# Qwiic_Hall_Effect_Sensor_TMAG5273.net
KiCad netlist of a schematic drawn in EAGLE
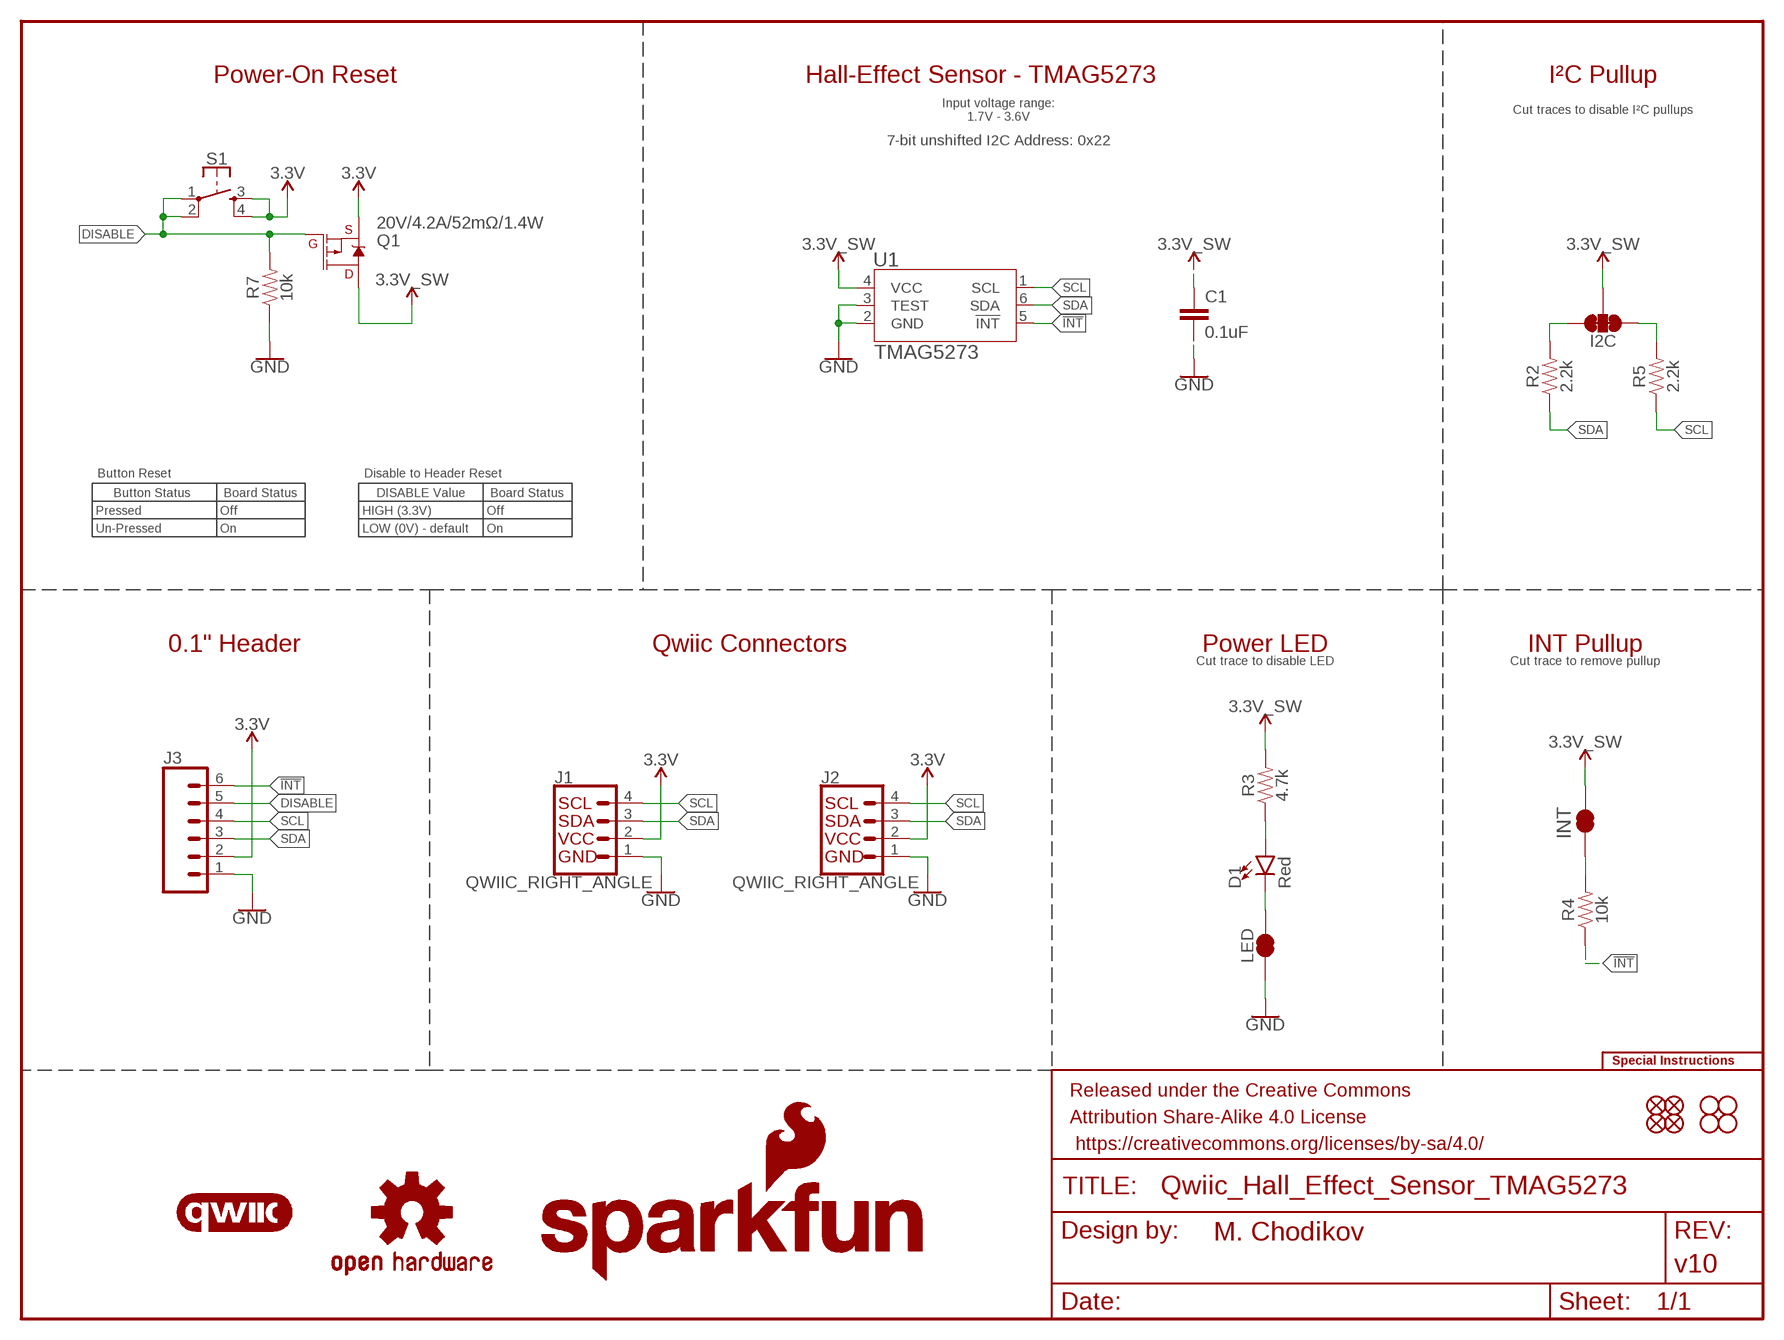
[diagram p0: schematic, sheet 1]

(export (version "E")
  (design (tool "Eeschema 10.0.6"))
  (components
    (comp (ref "C1")
      (value "0.1uF")
      (footprint "eagle-import:0603")
      (libsource (lib "eagle-import") (part "0.1UF-0603-25V-10%-X7R-WE"))
    )
    (comp (ref "D1")
      (value "Red")
      (footprint "eagle-import:LED-0603")
      (libsource (lib "eagle-import") (part "LED-RED_0603-KB"))
    )
    (comp (ref "FD1")
      (value "FIDUCIAL1X2")
      (footprint "eagle-import:FIDUCIAL-1X2")
      (libsource (lib "eagle-import") (part "FIDUCIAL1X2"))
    )
    (comp (ref "FD2")
      (value "FIDUCIAL1X2")
      (footprint "eagle-import:FIDUCIAL-1X2")
      (libsource (lib "eagle-import") (part "FIDUCIAL1X2"))
    )
    (comp (ref "FD3")
      (value "FIDUCIAL1X2")
      (footprint "eagle-import:FIDUCIAL-1X2")
      (libsource (lib "eagle-import") (part "FIDUCIAL1X2"))
    )
    (comp (ref "FD4")
      (value "FIDUCIAL1X2")
      (footprint "eagle-import:FIDUCIAL-1X2")
      (libsource (lib "eagle-import") (part "FIDUCIAL1X2"))
    )
    (comp (ref "FRAME1")
      (value "FRAME-LETTER")
      (footprint "eagle-import:CREATIVE_COMMONS")
      (fields (field (name "DESIGNER") "M. Chodikov") (field (name "REV") "v10"))
      (libsource (lib "eagle-import") (part "FRAME-LETTER"))
    )
    (comp (ref "H1")
      (value "STAND-OFF")
      (footprint "eagle-import:STAND-OFF")
      (libsource (lib "eagle-import") (part "STAND-OFF"))
    )
    (comp (ref "H2")
      (value "STAND-OFF")
      (footprint "eagle-import:STAND-OFF")
      (libsource (lib "eagle-import") (part "STAND-OFF"))
    )
    (comp (ref "H3")
      (value "STAND-OFF")
      (footprint "eagle-import:STAND-OFF")
      (libsource (lib "eagle-import") (part "STAND-OFF"))
    )
    (comp (ref "H4")
      (value "STAND-OFF")
      (footprint "eagle-import:STAND-OFF")
      (libsource (lib "eagle-import") (part "STAND-OFF"))
    )
    (comp (ref "I2C")
      (value "JUMPER-SMT_3_2-NC_TRACE_SILK")
      (footprint "eagle-import:SMT-JUMPER_3_2-NC_TRACE_SILK")
      (libsource (lib "eagle-import") (part "JUMPER-SMT_3_2-NC_TRACE_SILK"))
    )
    (comp (ref "J1")
      (value "QWIIC_RIGHT_ANGLE")
      (footprint "eagle-import:JST04_1MM_RA")
      (libsource (lib "eagle-import") (part "QWIIC_CONNECTORJS-1MM"))
    )
    (comp (ref "J2")
      (value "QWIIC_RIGHT_ANGLE")
      (footprint "eagle-import:JST04_1MM_RA")
      (libsource (lib "eagle-import") (part "QWIIC_CONNECTORJS-1MM"))
    )
    (comp (ref "J3")
      (value "CONN_06NO_SILK_FEMALE_PTH")
      (footprint "eagle-import:1X06_NO_SILK")
      (libsource (lib "eagle-import") (part "CONN_06NO_SILK_FEMALE_PTH"))
    )
    (comp (ref "JP2")
      (value "JUMPER-SMT_2_NC_TRACE_SILK")
      (footprint "eagle-import:SMT-JUMPER_2_NC_TRACE_SILK")
      (libsource (lib "eagle-import") (part "JUMPER-SMT_2_NC_TRACE_SILK"))
    )
    (comp (ref "LED")
      (value "JUMPER-SMT_2_NC_TRACE_SILK")
      (footprint "eagle-import:SMT-JUMPER_2_NC_TRACE_SILK")
      (libsource (lib "eagle-import") (part "JUMPER-SMT_2_NC_TRACE_SILK"))
    )
    (comp (ref "LOGO1")
      (value "OSHW-LOGOS")
      (footprint "eagle-import:OSHW-LOGO-S")
      (libsource (lib "eagle-import") (part "OSHW-LOGOS"))
    )
    (comp (ref "LOGO2")
      (value "SFE_LOGO_NAME_FLAME.1_INCH")
      (footprint "eagle-import:SFE_LOGO_NAME_FLAME_.1")
      (libsource (lib "eagle-import") (part "SFE_LOGO_NAME_FLAME.1_INCH"))
    )
    (comp (ref "LOGO3")
      (value "QWIIC_LOGO_4MM")
      (footprint "eagle-import:QWIIC_4MM")
      (libsource (lib "eagle-import") (part "QWIIC_LOGO_4MM"))
    )
    (comp (ref "LOGO4")
      (value "SFE_LOGO_NAME8_MM")
      (footprint "eagle-import:SFE_LOGO_NAME_8MM")
      (libsource (lib "eagle-import") (part "SFE_LOGO_NAME8_MM"))
    )
    (comp (ref "LOGO5")
      (value "SPECIAL_INSTRUCTIONS-ORDERING")
      (footprint "eagle-import:ORDERING_INSTRUCTIONS")
      (libsource (lib "eagle-import") (part "SPECIAL_INSTRUCTIONS-ORDERING"))
    )
    (comp (ref "LOGO6")
      (value "SFE_LOGO_FLAME.1_INCH")
      (footprint "eagle-import:SFE_LOGO_FLAME_.1")
      (libsource (lib "eagle-import") (part "SFE_LOGO_FLAME.1_INCH"))
    )
    (comp (ref "Q1")
      (value "20V/4.2A/52mΩ/1.4W")
      (footprint "eagle-import:SOT23-3")
      (libsource (lib "eagle-import") (part "MOSFET_PCH-DMG2305UX-7"))
    )
    (comp (ref "R2")
      (value "2.2k")
      (footprint "eagle-import:0603")
      (libsource (lib "eagle-import") (part "2.2KOHM-0603-1/10W-1%"))
    )
    (comp (ref "R3")
      (value "4.7k")
      (footprint "eagle-import:0603")
      (libsource (lib "eagle-import") (part "4.7KOHM-0603-1/10W-1%"))
    )
    (comp (ref "R4")
      (value "10k")
      (footprint "eagle-import:0603")
      (libsource (lib "eagle-import") (part "10KOHM-0603-1/10W-1%"))
    )
    (comp (ref "R5")
      (value "2.2k")
      (footprint "eagle-import:0603")
      (libsource (lib "eagle-import") (part "2.2KOHM-0603-1/10W-1%"))
    )
    (comp (ref "R7")
      (value "10k")
      (footprint "eagle-import:0603")
      (libsource (lib "eagle-import") (part "10KOHM-0603-1/10W-1%"))
    )
    (comp (ref "S1")
      (value "MOMENTARY-SWITCH-SPST-2-SMD-4.6X2.8MM")
      (footprint "eagle-import:TACTILE_SWITCH_SMD_4.6X2.8MM")
      (libsource (lib "eagle-import") (part "MOMENTARY-SWITCH-SPST-2-SMD-4.6X2.8MM"))
    )
    (comp (ref "U1")
      (value "TMAG5273")
      (footprint "eagle-import:SOT23-6_DBV_TEX")
      (libsource (lib "eagle-import") (part "TMAG5273A1QDBVT"))
    )
  )
  (nets
    (net (code "1") (name "/~{INT}") (class "Default")
      (node (ref "J3") (pin "6") (pinfunction "6_6") (pintype "passive"))
      (node (ref "R4") (pin "1") (pinfunction "1_1") (pintype "passive"))
      (node (ref "U1") (pin "5") (pinfunction "~{INT}_5") (pintype "bidirectional"))
    )
    (net (code "2") (name "3.3V") (class "Default")
      (node (ref "J1") (pin "2") (pinfunction "2_2") (pintype "power_in"))
      (node (ref "J2") (pin "2") (pinfunction "2_2") (pintype "power_in"))
      (node (ref "J3") (pin "2") (pinfunction "2_2") (pintype "passive"))
      (node (ref "Q1") (pin "2") (pinfunction "S_2") (pintype "bidirectional"))
      (node (ref "S1") (pin "3") (pinfunction "3_3") (pintype "passive"))
      (node (ref "S1") (pin "4") (pinfunction "4_4") (pintype "passive"))
    )
    (net (code "3") (name "3.3V_SW") (class "Default")
      (node (ref "C1") (pin "1") (pinfunction "1_1") (pintype "passive"))
      (node (ref "I2C") (pin "2") (pinfunction "2_2") (pintype "passive"))
      (node (ref "JP2") (pin "2") (pinfunction "2_2") (pintype "passive"))
      (node (ref "Q1") (pin "3") (pinfunction "D_3") (pintype "bidirectional"))
      (node (ref "R3") (pin "2") (pinfunction "2_2") (pintype "passive"))
      (node (ref "U1") (pin "4") (pinfunction "VCC_4") (pintype "power_in"))
    )
    (net (code "4") (name "DISABLE") (class "Default")
      (node (ref "J3") (pin "5") (pinfunction "5_5") (pintype "passive"))
      (node (ref "Q1") (pin "1") (pinfunction "G_1") (pintype "bidirectional"))
      (node (ref "R7") (pin "2") (pinfunction "2_2") (pintype "passive"))
      (node (ref "S1") (pin "1") (pinfunction "1_1") (pintype "passive"))
      (node (ref "S1") (pin "2") (pinfunction "2_2") (pintype "passive"))
    )
    (net (code "5") (name "GND") (class "Default")
      (node (ref "C1") (pin "2") (pinfunction "2_2") (pintype "passive"))
      (node (ref "J1") (pin "1") (pinfunction "1_1") (pintype "power_in"))
      (node (ref "J2") (pin "1") (pinfunction "1_1") (pintype "power_in"))
      (node (ref "J3") (pin "1") (pinfunction "1_1") (pintype "passive"))
      (node (ref "LED") (pin "1") (pinfunction "1_1") (pintype "passive"))
      (node (ref "R7") (pin "1") (pinfunction "1_1") (pintype "passive"))
      (node (ref "U1") (pin "2") (pinfunction "GND_2") (pintype "passive"))
      (node (ref "U1") (pin "3") (pinfunction "TEST_3") (pintype "input"))
    )
    (net (code "6") (name "Net-(D1-PadA)") (class "Default")
      (node (ref "D1") (pin "A") (pinfunction "A_A") (pintype "passive"))
      (node (ref "R3") (pin "1") (pinfunction "1_1") (pintype "passive"))
    )
    (net (code "7") (name "Net-(D1-PadC)") (class "Default")
      (node (ref "D1") (pin "C") (pinfunction "C_C") (pintype "passive"))
      (node (ref "LED") (pin "2") (pinfunction "2_2") (pintype "passive"))
    )
    (net (code "8") (name "Net-(I2C-Pad1)") (class "Default")
      (node (ref "I2C") (pin "1") (pinfunction "1_1") (pintype "passive"))
      (node (ref "R5") (pin "2") (pinfunction "2_2") (pintype "passive"))
    )
    (net (code "9") (name "Net-(I2C-Pad3)") (class "Default")
      (node (ref "I2C") (pin "3") (pinfunction "3_3") (pintype "passive"))
      (node (ref "R2") (pin "2") (pinfunction "2_2") (pintype "passive"))
    )
    (net (code "10") (name "Net-(JP2-Pad1)") (class "Default")
      (node (ref "JP2") (pin "1") (pinfunction "1_1") (pintype "passive"))
      (node (ref "R4") (pin "2") (pinfunction "2_2") (pintype "passive"))
    )
    (net (code "11") (name "SCL") (class "Default")
      (node (ref "J1") (pin "4") (pinfunction "4_4") (pintype "passive"))
      (node (ref "J2") (pin "4") (pinfunction "4_4") (pintype "passive"))
      (node (ref "J3") (pin "4") (pinfunction "4_4") (pintype "passive"))
      (node (ref "R5") (pin "1") (pinfunction "1_1") (pintype "passive"))
      (node (ref "U1") (pin "1") (pinfunction "SCL_1") (pintype "bidirectional"))
    )
    (net (code "12") (name "SDA") (class "Default")
      (node (ref "J1") (pin "3") (pinfunction "3_3") (pintype "passive"))
      (node (ref "J2") (pin "3") (pinfunction "3_3") (pintype "passive"))
      (node (ref "J3") (pin "3") (pinfunction "3_3") (pintype "passive"))
      (node (ref "R2") (pin "1") (pinfunction "1_1") (pintype "passive"))
      (node (ref "U1") (pin "6") (pinfunction "SDA_6") (pintype "bidirectional"))
    )
  )
)
